# USB_Switch_Tester.net
KiCad netlist of a schematic drawn in EAGLE
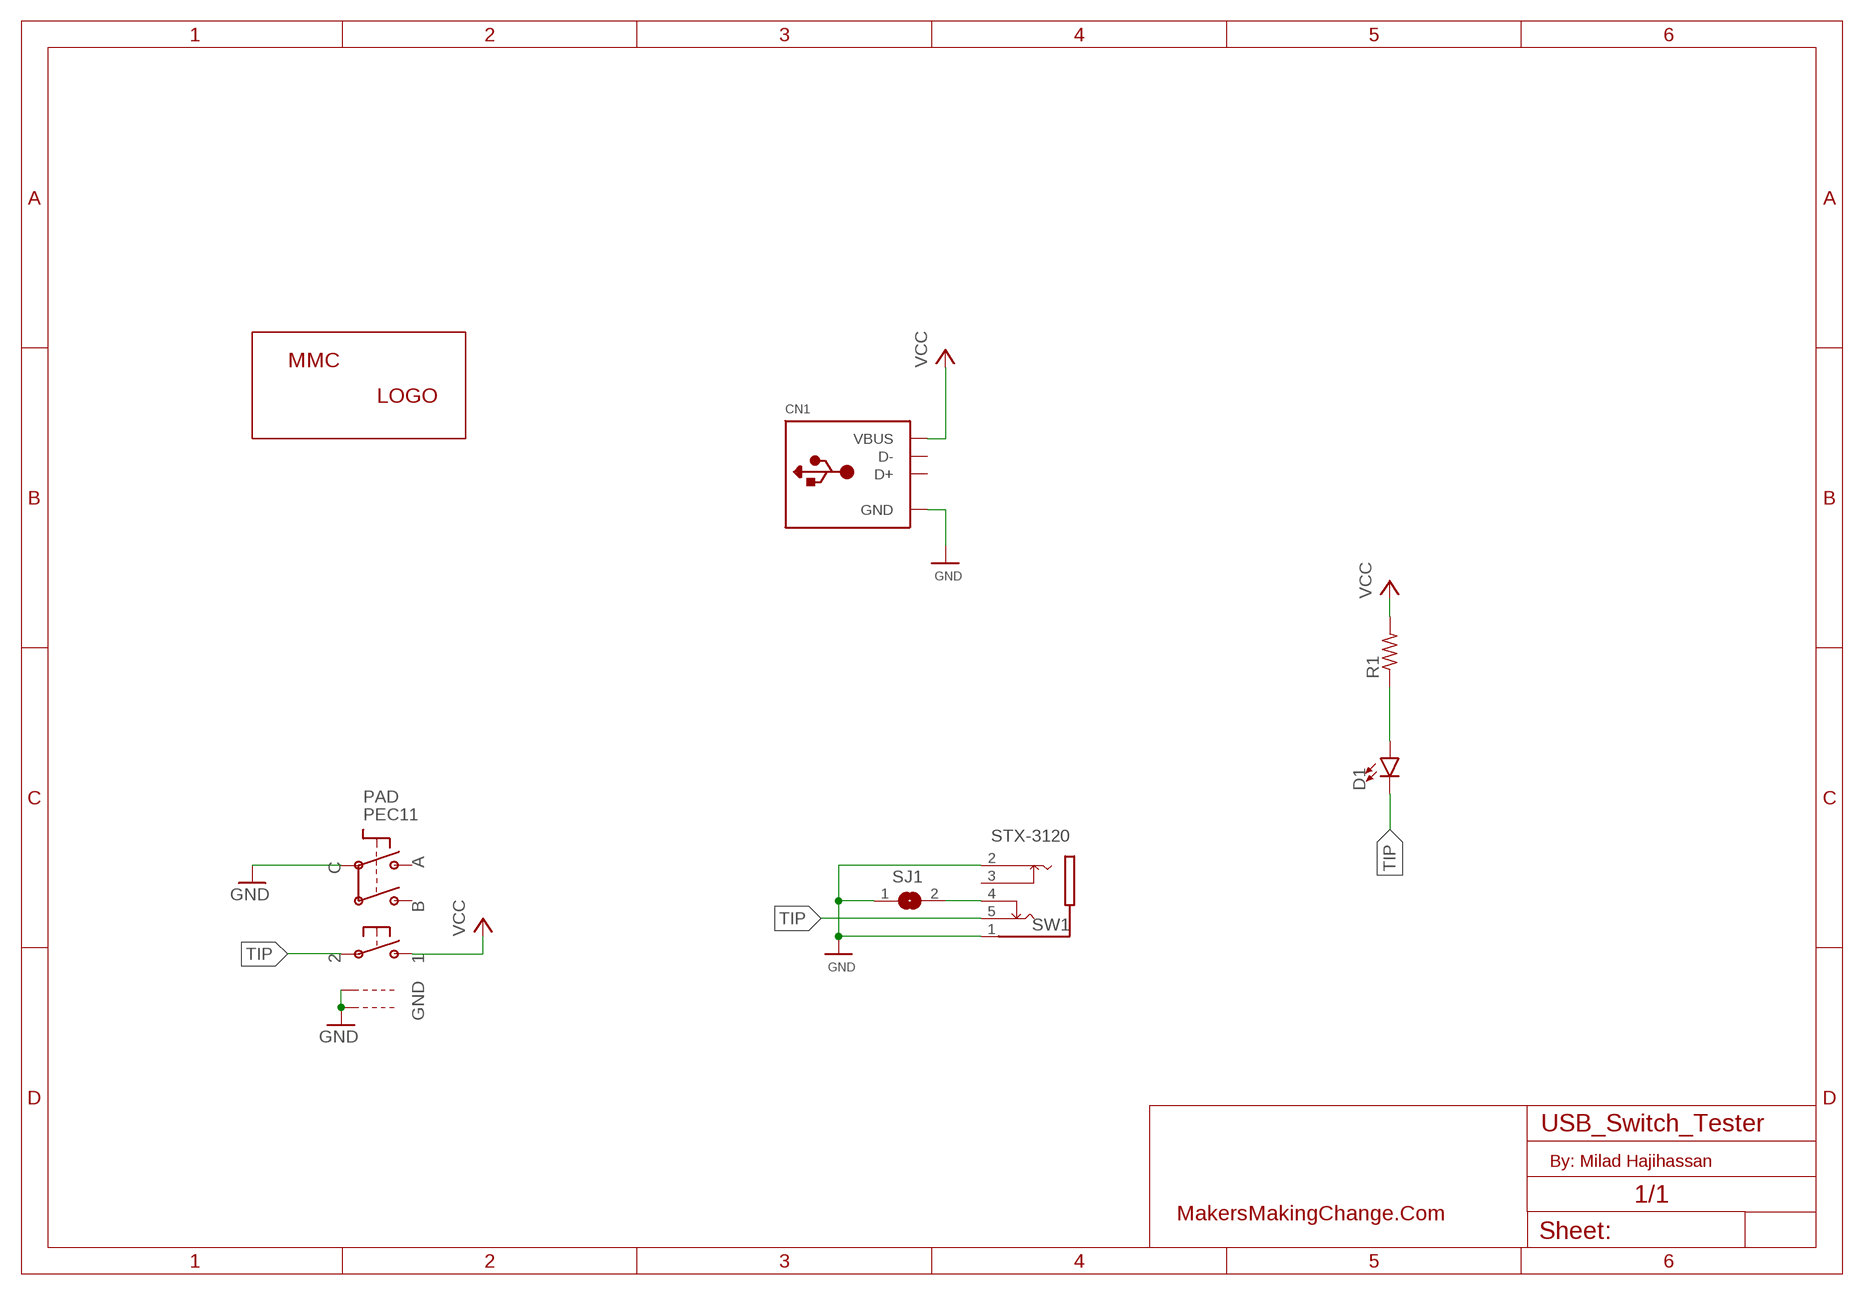
[diagram p0: schematic, sheet 1]

(export (version "E")
  (design (tool "Eeschema 10.0.6"))
  (components
    (comp (ref "CN1")
      (value "MICROBUILDER_USB_TYPEAPCB")
      (footprint "eagle-import:MICROBUILDER_USBA_PCB")
      (libsource (lib "eagle-import") (part "MICROBUILDER_USB_TYPEAPCB"))
    )
    (comp (ref "D1")
      (value "LED_5MM-5MM-RED")
      (footprint "eagle-import:LED_5MM_RED")
      (libsource (lib "eagle-import") (part "LED_5MM-5MM-RED"))
    )
    (comp (ref "LABEL_LOGO")
      (value "MMC_LOGO-XSM")
      (footprint "eagle-import:MMC_X-SMALL_LOGO")
      (libsource (lib "eagle-import") (part "MMC_LOGO-XSM"))
    )
    (comp (ref "PAD")
      (value "PEC11")
      (footprint "eagle-import:ADAFRUIT_ELECTROMECH_PEC11+SWITCH")
      (libsource (lib "eagle-import") (part "ADAFRUIT_ELECTROMECH_ENCODER_PLUS_SWITCH_PEC11_BOURNS"))
    )
    (comp (ref "R1")
      (value "RESISTOR-US-0204/5")
      (footprint "eagle-import:RESISTOR_0204_5")
      (libsource (lib "eagle-import") (part "RESISTOR-US-0204/5"))
    )
    (comp (ref "SJ1")
      (value "SOLDERJUMPERREFLOW")
      (footprint "eagle-import:SOLDERJUMPER_REFLOW")
      (libsource (lib "eagle-import") (part "SOLDERJUMPERREFLOW"))
    )
    (comp (ref "SW1")
      (value "STX-3120")
      (footprint "eagle-import:STX-3120-5B")
      (libsource (lib "eagle-import") (part "STX-3120-5B"))
    )
  )
  (nets
    (net (code "1") (name "GND") (class "Default")
      (node (ref "CN1") (pin "GND") (pinfunction "GND_GND") (pintype "power_in"))
      (node (ref "PAD") (pin "P$C") (pinfunction "P$C_P$C") (pintype "passive"))
      (node (ref "PAD") (pin "P$GND1") (pinfunction "P$GND1_P$GND1") (pintype "passive"))
      (node (ref "PAD") (pin "P$GND2") (pinfunction "P$GND2_P$GND2") (pintype "passive"))
      (node (ref "SJ1") (pin "1") (pinfunction "1_1") (pintype "passive"))
      (node (ref "SW1") (pin "1") (pinfunction "1_1") (pintype "passive"))
      (node (ref "SW1") (pin "2") (pinfunction "2_2") (pintype "passive"))
    )
    (net (code "2") (name "Net-(D1-PadA)") (class "Default")
      (node (ref "D1") (pin "A") (pinfunction "A_A") (pintype "passive"))
      (node (ref "R1") (pin "1") (pinfunction "1_1") (pintype "passive"))
    )
    (net (code "3") (name "Net-(SJ1-Pad2)") (class "Default")
      (node (ref "SJ1") (pin "2") (pinfunction "2_2") (pintype "passive"))
      (node (ref "SW1") (pin "4") (pinfunction "4_4") (pintype "passive"))
    )
    (net (code "4") (name "TIP") (class "Default")
      (node (ref "D1") (pin "K") (pinfunction "C_K") (pintype "passive"))
      (node (ref "PAD") (pin "P$2") (pinfunction "P$2_P$2") (pintype "passive"))
      (node (ref "SW1") (pin "5") (pinfunction "5_5") (pintype "passive"))
    )
    (net (code "5") (name "VCC") (class "Default")
      (node (ref "CN1") (pin "VCC") (pinfunction "VBUS_VCC") (pintype "power_in"))
      (node (ref "PAD") (pin "P$1") (pinfunction "P$1_P$1") (pintype "passive"))
      (node (ref "R1") (pin "2") (pinfunction "2_2") (pintype "passive"))
    )
    (net (code "6") (name "unconnected-(CN1-D+-PadUSB_PLUS)") (class "Default")
      (node (ref "CN1") (pin "USB_PLUS") (pinfunction "D+_USB_PLUS") (pintype "bidirectional"))
    )
    (net (code "7") (name "unconnected-(CN1-D--PadUSB_NEG)") (class "Default")
      (node (ref "CN1") (pin "USB_NEG") (pinfunction "D-_USB_NEG") (pintype "bidirectional"))
    )
    (net (code "8") (name "unconnected-(PAD-PadP$A)") (class "Default")
      (node (ref "PAD") (pin "P$A") (pinfunction "P$A_P$A") (pintype "passive"))
    )
    (net (code "9") (name "unconnected-(PAD-PadP$B)") (class "Default")
      (node (ref "PAD") (pin "P$B") (pinfunction "P$B_P$B") (pintype "passive"))
    )
    (net (code "10") (name "unconnected-(SW1-Pad3)") (class "Default")
      (node (ref "SW1") (pin "3") (pinfunction "3_3") (pintype "passive"))
    )
  )
)
